# DronePCB_1.net
KiCad netlist of a schematic drawn in Altium Designer
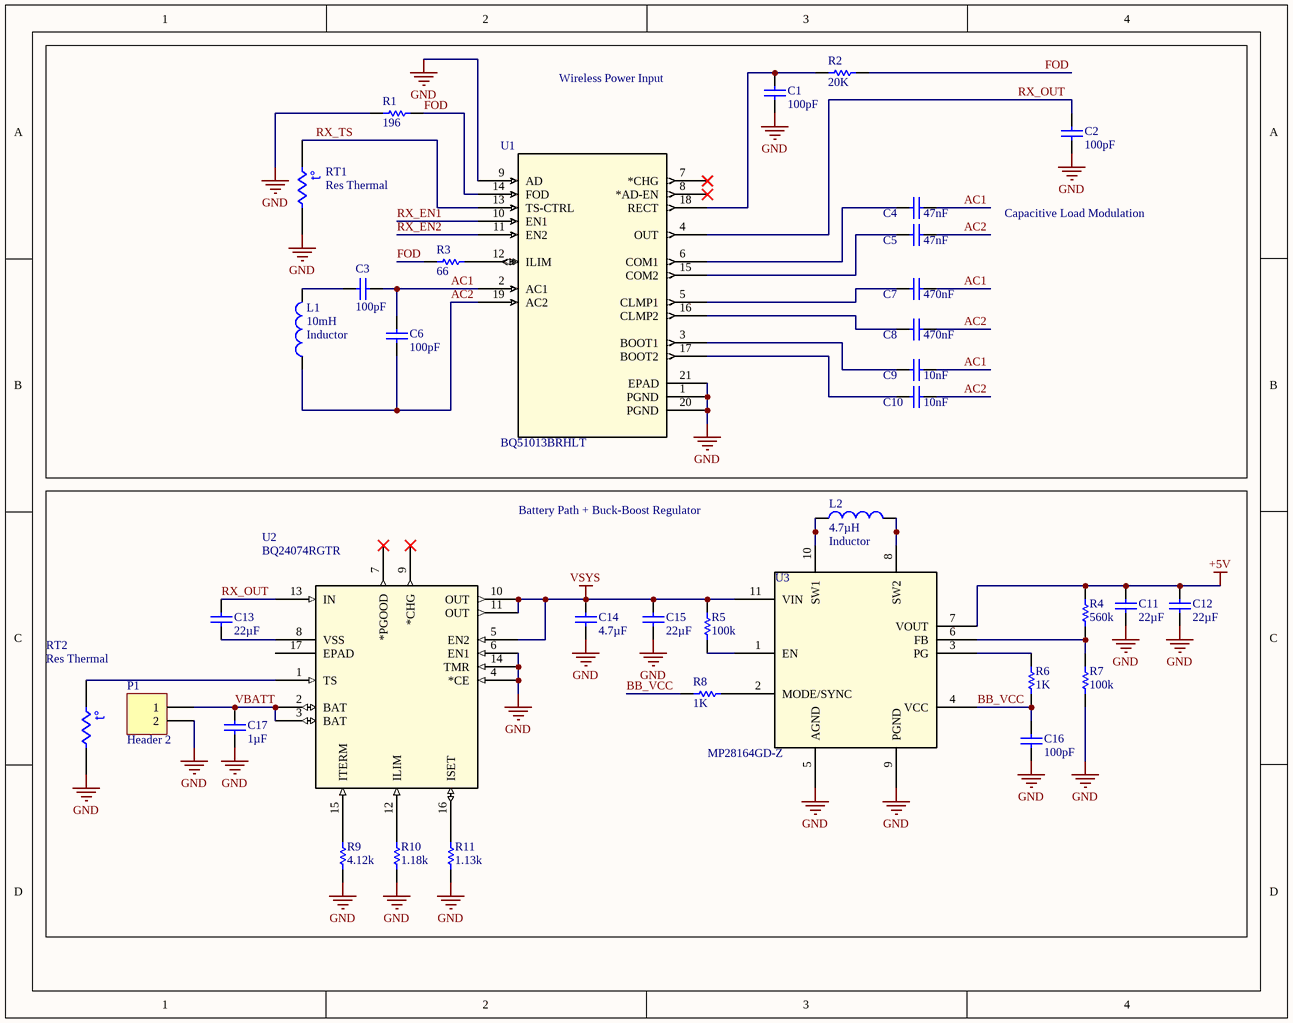
[diagram p0: DronePCB_1.SchDoc]

(export (version "E")
  (design (tool "Eeschema 10.0.6"))
  (components
    (comp (ref "C1")
      (value "100pF")
      (footprint "RAD-0.3")
      (description "Capacitor")
      (fields (field (name "Comment") "Cap") (field (name "PUBLISHER") "Altium Limited"))
      (libsource (lib "Miscellaneous Devices") (part "Cap"))
    )
    (comp (ref "C2")
      (value "100pF")
      (footprint "RAD-0.3")
      (description "Capacitor")
      (fields (field (name "Comment") "Cap") (field (name "PUBLISHER") "Altium Limited"))
      (libsource (lib "Miscellaneous Devices") (part "Cap"))
    )
    (comp (ref "C3")
      (value "100pF")
      (footprint "RAD-0.3")
      (description "Capacitor")
      (fields (field (name "Comment") "Cap") (field (name "PUBLISHER") "Altium Limited"))
      (libsource (lib "Miscellaneous Devices") (part "Cap"))
    )
    (comp (ref "C4")
      (value "47nF")
      (footprint "RAD-0.3")
      (description "Capacitor")
      (fields (field (name "Comment") "Cap") (field (name "PUBLISHER") "Altium Limited"))
      (libsource (lib "Miscellaneous Devices") (part "Cap"))
    )
    (comp (ref "C5")
      (value "47nF")
      (footprint "RAD-0.3")
      (description "Capacitor")
      (fields (field (name "Comment") "Cap") (field (name "PUBLISHER") "Altium Limited"))
      (libsource (lib "Miscellaneous Devices") (part "Cap"))
    )
    (comp (ref "C6")
      (value "100pF")
      (footprint "RAD-0.3")
      (description "Capacitor")
      (fields (field (name "Comment") "Cap") (field (name "PUBLISHER") "Altium Limited"))
      (libsource (lib "Miscellaneous Devices") (part "Cap"))
    )
    (comp (ref "C7")
      (value "470nF")
      (footprint "RAD-0.3")
      (description "Capacitor")
      (fields (field (name "Comment") "Cap") (field (name "PUBLISHER") "Altium Limited"))
      (libsource (lib "Miscellaneous Devices") (part "Cap"))
    )
    (comp (ref "C8")
      (value "470nF")
      (footprint "RAD-0.3")
      (description "Capacitor")
      (fields (field (name "Comment") "Cap") (field (name "PUBLISHER") "Altium Limited"))
      (libsource (lib "Miscellaneous Devices") (part "Cap"))
    )
    (comp (ref "C9")
      (value "10nF")
      (footprint "RAD-0.3")
      (description "Capacitor")
      (fields (field (name "Comment") "Cap") (field (name "PUBLISHER") "Altium Limited"))
      (libsource (lib "Miscellaneous Devices") (part "Cap"))
    )
    (comp (ref "C10")
      (value "10nF")
      (footprint "RAD-0.3")
      (description "Capacitor")
      (fields (field (name "Comment") "Cap") (field (name "PUBLISHER") "Altium Limited"))
      (libsource (lib "Miscellaneous Devices") (part "Cap"))
    )
    (comp (ref "C11")
      (value "22µF")
      (footprint "RAD-0.3")
      (description "Capacitor")
      (fields (field (name "Comment") "Cap") (field (name "PUBLISHER") "Altium Limited"))
      (libsource (lib "Miscellaneous Devices") (part "Cap"))
    )
    (comp (ref "C12")
      (value "22µF")
      (footprint "RAD-0.3")
      (description "Capacitor")
      (fields (field (name "Comment") "Cap") (field (name "PUBLISHER") "Altium Limited"))
      (libsource (lib "Miscellaneous Devices") (part "Cap"))
    )
    (comp (ref "C13")
      (value "22µF")
      (footprint "RAD-0.3")
      (description "Capacitor")
      (fields (field (name "Comment") "Cap") (field (name "PUBLISHER") "Altium Limited"))
      (libsource (lib "Miscellaneous Devices") (part "Cap"))
    )
    (comp (ref "C14")
      (value "4.7µF")
      (footprint "RAD-0.3")
      (description "Capacitor")
      (fields (field (name "Comment") "Cap") (field (name "PUBLISHER") "Altium Limited"))
      (libsource (lib "Miscellaneous Devices") (part "Cap"))
    )
    (comp (ref "C15")
      (value "22µF")
      (footprint "RAD-0.3")
      (description "Capacitor")
      (fields (field (name "Comment") "Cap") (field (name "PUBLISHER") "Altium Limited"))
      (libsource (lib "Miscellaneous Devices") (part "Cap"))
    )
    (comp (ref "C16")
      (value "100pF")
      (footprint "RAD-0.3")
      (description "Capacitor")
      (fields (field (name "Comment") "Cap") (field (name "PUBLISHER") "Altium Limited"))
      (libsource (lib "Miscellaneous Devices") (part "Cap"))
    )
    (comp (ref "C17")
      (value "1µF")
      (footprint "RAD-0.3")
      (description "Capacitor")
      (fields (field (name "Comment") "Cap") (field (name "PUBLISHER") "Altium Limited"))
      (libsource (lib "Miscellaneous Devices") (part "Cap"))
    )
    (comp (ref "L1")
      (value "Inductor")
      (footprint "0402-A")
      (fields (field (name "ALTIUM_VALUE") "10mH") (field (name "PUBLISHER") "Altium Limited"))
      (libsource (lib "Miscellaneous Devices") (part "Inductor"))
    )
    (comp (ref "L2")
      (value "Inductor")
      (footprint "0402-A")
      (fields (field (name "ALTIUM_VALUE") "4.7µH") (field (name "PUBLISHER") "Altium Limited"))
      (libsource (lib "Miscellaneous Devices") (part "Inductor"))
    )
    (comp (ref "P1")
      (value "Header 2")
      (footprint "CUI_TB002-500-02BE")
      (description "Header, 2-Pin")
      (fields (field (name "PUBLISHER") "Altium Limited"))
      (libsource (lib "Miscellaneous Connectors") (part "Header 2"))
    )
    (comp (ref "R1")
      (value "196")
      (footprint "AXIAL-0.3")
      (description "Resistor")
      (fields (field (name "Comment") "Res1") (field (name "PUBLISHER") "Altium Limited"))
      (libsource (lib "Miscellaneous Devices") (part "Res1"))
    )
    (comp (ref "R2")
      (value "20K")
      (footprint "AXIAL-0.3")
      (description "Resistor")
      (fields (field (name "Comment") "Res1") (field (name "PUBLISHER") "Altium Limited"))
      (libsource (lib "Miscellaneous Devices") (part "Res1"))
    )
    (comp (ref "R3")
      (value "66")
      (footprint "AXIAL-0.3")
      (description "Resistor")
      (fields (field (name "Comment") "Res1") (field (name "PUBLISHER") "Altium Limited"))
      (libsource (lib "Miscellaneous Devices") (part "Res1"))
    )
    (comp (ref "R4")
      (value "560k")
      (footprint "AXIAL-0.3")
      (description "Resistor")
      (fields (field (name "Comment") "Res1") (field (name "PUBLISHER") "Altium Limited"))
      (libsource (lib "Miscellaneous Devices") (part "Res1"))
    )
    (comp (ref "R5")
      (value "100k")
      (footprint "AXIAL-0.3")
      (description "Resistor")
      (fields (field (name "Comment") "Res1") (field (name "PUBLISHER") "Altium Limited"))
      (libsource (lib "Miscellaneous Devices") (part "Res1"))
    )
    (comp (ref "R6")
      (value "1K")
      (footprint "AXIAL-0.3")
      (description "Resistor")
      (fields (field (name "Comment") "Res1") (field (name "PUBLISHER") "Altium Limited"))
      (libsource (lib "Miscellaneous Devices") (part "Res1"))
    )
    (comp (ref "R7")
      (value "100k")
      (footprint "AXIAL-0.3")
      (description "Resistor")
      (fields (field (name "Comment") "Res1") (field (name "PUBLISHER") "Altium Limited"))
      (libsource (lib "Miscellaneous Devices") (part "Res1"))
    )
    (comp (ref "R8")
      (value "1K")
      (footprint "AXIAL-0.3")
      (description "Resistor")
      (fields (field (name "Comment") "Res1") (field (name "PUBLISHER") "Altium Limited"))
      (libsource (lib "Miscellaneous Devices") (part "Res1"))
    )
    (comp (ref "R9")
      (value "4.12k")
      (footprint "AXIAL-0.3")
      (description "Resistor")
      (fields (field (name "Comment") "Res1") (field (name "PUBLISHER") "Altium Limited"))
      (libsource (lib "Miscellaneous Devices") (part "Res1"))
    )
    (comp (ref "R10")
      (value "1.18k")
      (footprint "AXIAL-0.3")
      (description "Resistor")
      (fields (field (name "Comment") "Res1") (field (name "PUBLISHER") "Altium Limited"))
      (libsource (lib "Miscellaneous Devices") (part "Res1"))
    )
    (comp (ref "R11")
      (value "1.13k")
      (footprint "AXIAL-0.3")
      (description "Resistor")
      (fields (field (name "Comment") "Res1") (field (name "PUBLISHER") "Altium Limited"))
      (libsource (lib "Miscellaneous Devices") (part "Res1"))
    )
    (comp (ref "RT1")
      (value "Res Thermal")
      (footprint "6-0805_N")
      (description "Thermistor")
      (fields (field (name "PUBLISHER") "Altium Limited"))
      (libsource (lib "Miscellaneous Devices") (part "Res Thermal"))
    )
    (comp (ref "RT2")
      (value "Res Thermal")
      (footprint "6-0805_N")
      (description "Thermistor")
      (fields (field (name "PUBLISHER") "Altium Limited"))
      (libsource (lib "Miscellaneous Devices") (part "Res Thermal"))
    )
    (comp (ref "U1")
      (value "BQ51013BRHLT")
      (footprint "RHL20_2P05X3P05")
      (description "WPC 1.1 Compatible Fully integrated Wireless power Receiver IC 20-VQFN 0 to 125")
      (fields (field (name "COPYRIGHT") "Copyright (C) 2026 Ultra Librarian. All rights reserved."))
      (libsource (lib "DronePCB_Main") (part "BQ51013BRHLT"))
    )
    (comp (ref "U2")
      (value "BQ24074RGTR")
      (footprint "RGT16_1P7X1P7")
      (fields (field (name "COPYRIGHT") "Copyright (C) 2026 Ultra Librarian. All rights reserved."))
      (libsource (lib "DronePCB_Main") (part "BQ24074RGTR"))
    )
    (comp (ref "U3")
      (value "MP28164GD-Z")
      (footprint "QFN-11_MP28164_MNP")
      (description "High-Efficiency Single-Inductor Buck-Boost Converter with 4.2A Switches")
      (fields (field (name "COPYRIGHT") "Copyright (C) 2025 Ultra Librarian. All rights reserved."))
      (libsource (lib "DronePCB_Main") (part "MP28164GD-Z"))
    )
  )
  (nets
    (net (code "1") (name "+5V") (class "Default")
      (node (ref "C11") (pin "2") (pinfunction "2_2") (pintype "passive"))
      (node (ref "C12") (pin "2") (pinfunction "2_2") (pintype "passive"))
      (node (ref "R4") (pin "2") (pinfunction "2_2") (pintype "passive"))
      (node (ref "U3") (pin "7") (pinfunction "VOUT_7") (pintype "power_in"))
    )
    (net (code "2") (name "/AC1") (class "Default")
      (node (ref "C3") (pin "2") (pinfunction "2_2") (pintype "passive"))
      (node (ref "C4") (pin "2") (pinfunction "2_2") (pintype "passive"))
      (node (ref "C6") (pin "2") (pinfunction "2_2") (pintype "passive"))
      (node (ref "C7") (pin "2") (pinfunction "2_2") (pintype "passive"))
      (node (ref "C9") (pin "2") (pinfunction "2_2") (pintype "passive"))
      (node (ref "U1") (pin "2") (pinfunction "AC1_2") (pintype "input"))
    )
    (net (code "3") (name "/AC2") (class "Default")
      (node (ref "C10") (pin "2") (pinfunction "2_2") (pintype "passive"))
      (node (ref "C5") (pin "2") (pinfunction "2_2") (pintype "passive"))
      (node (ref "C6") (pin "1") (pinfunction "1_1") (pintype "passive"))
      (node (ref "C8") (pin "2") (pinfunction "2_2") (pintype "passive"))
      (node (ref "L1") (pin "1") (pinfunction "1_1") (pintype "passive"))
      (node (ref "U1") (pin "19") (pinfunction "AC2_19") (pintype "input"))
    )
    (net (code "4") (name "/BB_VCC") (class "Default")
      (node (ref "C16") (pin "2") (pinfunction "2_2") (pintype "passive"))
      (node (ref "R6") (pin "1") (pinfunction "1_1") (pintype "passive"))
      (node (ref "R8") (pin "2") (pinfunction "2_2") (pintype "passive"))
      (node (ref "U3") (pin "4") (pinfunction "VCC_4") (pintype "power_in"))
    )
    (net (code "5") (name "/FOD") (class "Default")
      (node (ref "R1") (pin "2") (pinfunction "2_2") (pintype "passive"))
      (node (ref "R2") (pin "2") (pinfunction "2_2") (pintype "passive"))
      (node (ref "R3") (pin "1") (pinfunction "1_1") (pintype "passive"))
      (node (ref "U1") (pin "14") (pinfunction "FOD_14") (pintype "input"))
    )
    (net (code "6") (name "/RX_EN1") (class "Default")
      (node (ref "U1") (pin "10") (pinfunction "EN1_10") (pintype "input"))
    )
    (net (code "7") (name "/RX_EN2") (class "Default")
      (node (ref "U1") (pin "11") (pinfunction "EN2_11") (pintype "input"))
    )
    (net (code "8") (name "/RX_OUT") (class "Default")
      (node (ref "C13") (pin "2") (pinfunction "2_2") (pintype "passive"))
      (node (ref "C2") (pin "1") (pinfunction "1_1") (pintype "passive"))
      (node (ref "U1") (pin "4") (pinfunction "OUT_4") (pintype "output"))
      (node (ref "U2") (pin "13") (pinfunction "IN_13") (pintype "input"))
    )
    (net (code "9") (name "/RX_TS") (class "Default")
      (node (ref "RT1") (pin "1") (pinfunction "1_1") (pintype "passive"))
      (node (ref "U1") (pin "13") (pinfunction "TS-CTRL_13") (pintype "input"))
    )
    (net (code "10") (name "/VBATT") (class "Default")
      (node (ref "C17") (pin "2") (pinfunction "2_2") (pintype "passive"))
      (node (ref "P1") (pin "1") (pinfunction "1_1") (pintype "passive"))
      (node (ref "U2") (pin "2") (pinfunction "BAT_2") (pintype "bidirectional"))
      (node (ref "U2") (pin "3") (pinfunction "BAT_3") (pintype "bidirectional"))
    )
    (net (code "11") (name "GND") (class "Default")
      (node (ref "C1") (pin "2") (pinfunction "2_2") (pintype "passive"))
      (node (ref "C11") (pin "1") (pinfunction "1_1") (pintype "passive"))
      (node (ref "C12") (pin "1") (pinfunction "1_1") (pintype "passive"))
      (node (ref "C14") (pin "1") (pinfunction "1_1") (pintype "passive"))
      (node (ref "C15") (pin "1") (pinfunction "1_1") (pintype "passive"))
      (node (ref "C16") (pin "1") (pinfunction "1_1") (pintype "passive"))
      (node (ref "C17") (pin "1") (pinfunction "1_1") (pintype "passive"))
      (node (ref "C2") (pin "2") (pinfunction "2_2") (pintype "passive"))
      (node (ref "P1") (pin "2") (pinfunction "2_2") (pintype "passive"))
      (node (ref "R1") (pin "1") (pinfunction "1_1") (pintype "passive"))
      (node (ref "R10") (pin "1") (pinfunction "1_1") (pintype "passive"))
      (node (ref "R11") (pin "1") (pinfunction "1_1") (pintype "passive"))
      (node (ref "R7") (pin "1") (pinfunction "1_1") (pintype "passive"))
      (node (ref "R9") (pin "1") (pinfunction "1_1") (pintype "passive"))
      (node (ref "RT1") (pin "2") (pinfunction "2_2") (pintype "passive"))
      (node (ref "RT2") (pin "2") (pinfunction "2_2") (pintype "passive"))
      (node (ref "U1") (pin "1") (pinfunction "PGND_1") (pintype "power_in"))
      (node (ref "U1") (pin "20") (pinfunction "PGND_20") (pintype "power_in"))
      (node (ref "U1") (pin "21") (pinfunction "EPAD_21") (pintype "passive"))
      (node (ref "U1") (pin "9") (pinfunction "AD_9") (pintype "input"))
      (node (ref "U2") (pin "14") (pinfunction "TMR_14") (pintype "input"))
      (node (ref "U2") (pin "4") (pinfunction "*CE_4") (pintype "input"))
      (node (ref "U2") (pin "6") (pinfunction "EN1_6") (pintype "input"))
      (node (ref "U3") (pin "5") (pinfunction "AGND_5") (pintype "power_in"))
      (node (ref "U3") (pin "9") (pinfunction "PGND_9") (pintype "power_in"))
    )
    (net (code "12") (name "Net-(C3-Pad1)") (class "Default")
      (node (ref "C3") (pin "1") (pinfunction "1_1") (pintype "passive"))
      (node (ref "L1") (pin "2") (pinfunction "2_2") (pintype "passive"))
    )
    (net (code "13") (name "Net-(U1-BOOT1)") (class "Default")
      (node (ref "C9") (pin "1") (pinfunction "1_1") (pintype "passive"))
      (node (ref "U1") (pin "3") (pinfunction "BOOT1_3") (pintype "output"))
    )
    (net (code "14") (name "Net-(U1-BOOT2)") (class "Default")
      (node (ref "C10") (pin "1") (pinfunction "1_1") (pintype "passive"))
      (node (ref "U1") (pin "17") (pinfunction "BOOT2_17") (pintype "output"))
    )
    (net (code "15") (name "Net-(U1-CLMP1)") (class "Default")
      (node (ref "C7") (pin "1") (pinfunction "1_1") (pintype "passive"))
      (node (ref "U1") (pin "5") (pinfunction "CLMP1_5") (pintype "output"))
    )
    (net (code "16") (name "Net-(U1-CLMP2)") (class "Default")
      (node (ref "C8") (pin "1") (pinfunction "1_1") (pintype "passive"))
      (node (ref "U1") (pin "16") (pinfunction "CLMP2_16") (pintype "output"))
    )
    (net (code "17") (name "Net-(U1-COM1)") (class "Default")
      (node (ref "C4") (pin "1") (pinfunction "1_1") (pintype "passive"))
      (node (ref "U1") (pin "6") (pinfunction "COM1_6") (pintype "output"))
    )
    (net (code "18") (name "Net-(U1-COM2)") (class "Default")
      (node (ref "C5") (pin "1") (pinfunction "1_1") (pintype "passive"))
      (node (ref "U1") (pin "15") (pinfunction "COM2_15") (pintype "output"))
    )
    (net (code "19") (name "Net-(U1-ILIM)") (class "Default")
      (node (ref "R3") (pin "2") (pinfunction "2_2") (pintype "passive"))
      (node (ref "U1") (pin "12") (pinfunction "ILIM_12") (pintype "bidirectional"))
    )
    (net (code "20") (name "Net-(U1-RECT)") (class "Default")
      (node (ref "C1") (pin "1") (pinfunction "1_1") (pintype "passive"))
      (node (ref "R2") (pin "1") (pinfunction "1_1") (pintype "passive"))
      (node (ref "U1") (pin "18") (pinfunction "RECT_18") (pintype "output"))
    )
    (net (code "21") (name "Net-(U2-ILIM)") (class "Default")
      (node (ref "R10") (pin "2") (pinfunction "2_2") (pintype "passive"))
      (node (ref "U2") (pin "12") (pinfunction "ILIM_12") (pintype "input"))
    )
    (net (code "22") (name "Net-(U2-ISET)") (class "Default")
      (node (ref "R11") (pin "2") (pinfunction "2_2") (pintype "passive"))
      (node (ref "U2") (pin "16") (pinfunction "ISET_16") (pintype "bidirectional"))
    )
    (net (code "23") (name "Net-(U2-ITERM)") (class "Default")
      (node (ref "R9") (pin "2") (pinfunction "2_2") (pintype "passive"))
      (node (ref "U2") (pin "15") (pinfunction "ITERM_15") (pintype "input"))
    )
    (net (code "24") (name "Net-(U2-TS)") (class "Default")
      (node (ref "RT2") (pin "1") (pinfunction "1_1") (pintype "passive"))
      (node (ref "U2") (pin "1") (pinfunction "TS_1") (pintype "input"))
    )
    (net (code "25") (name "Net-(U2-VSS)") (class "Default")
      (node (ref "C13") (pin "1") (pinfunction "1_1") (pintype "passive"))
      (node (ref "U2") (pin "8") (pinfunction "VSS_8") (pintype "power_in"))
    )
    (net (code "26") (name "Net-(U3-EN)") (class "Default")
      (node (ref "R5") (pin "2") (pinfunction "2_2") (pintype "passive"))
      (node (ref "U3") (pin "1") (pinfunction "EN_1") (pintype "passive"))
    )
    (net (code "27") (name "Net-(U3-FB)") (class "Default")
      (node (ref "R4") (pin "1") (pinfunction "1_1") (pintype "passive"))
      (node (ref "R7") (pin "2") (pinfunction "2_2") (pintype "passive"))
      (node (ref "U3") (pin "6") (pinfunction "FB_6") (pintype "passive"))
    )
    (net (code "28") (name "Net-(U3-MODE{slash}SYNC)") (class "Default")
      (node (ref "R8") (pin "1") (pinfunction "1_1") (pintype "passive"))
      (node (ref "U3") (pin "2") (pinfunction "MODE/SYNC_2") (pintype "passive"))
    )
    (net (code "29") (name "Net-(U3-PG)") (class "Default")
      (node (ref "R6") (pin "2") (pinfunction "2_2") (pintype "passive"))
      (node (ref "U3") (pin "3") (pinfunction "PG_3") (pintype "passive"))
    )
    (net (code "30") (name "Net-(U3-SW1)") (class "Default")
      (node (ref "L2") (pin "1") (pinfunction "1_1") (pintype "passive"))
      (node (ref "U3") (pin "10") (pinfunction "SW1_10") (pintype "passive"))
    )
    (net (code "31") (name "Net-(U3-SW2)") (class "Default")
      (node (ref "L2") (pin "2") (pinfunction "2_2") (pintype "passive"))
      (node (ref "U3") (pin "8") (pinfunction "SW2_8") (pintype "passive"))
    )
    (net (code "32") (name "VSYS") (class "Default")
      (node (ref "C14") (pin "2") (pinfunction "2_2") (pintype "passive"))
      (node (ref "C15") (pin "2") (pinfunction "2_2") (pintype "passive"))
      (node (ref "R5") (pin "1") (pinfunction "1_1") (pintype "passive"))
      (node (ref "U2") (pin "10") (pinfunction "OUT_10") (pintype "output"))
      (node (ref "U2") (pin "11") (pinfunction "OUT_11") (pintype "output"))
      (node (ref "U2") (pin "5") (pinfunction "EN2_5") (pintype "input"))
      (node (ref "U3") (pin "11") (pinfunction "VIN_11") (pintype "power_in"))
    )
    (net (code "33") (name "unconnected-(U1-*AD-EN-Pad8)") (class "Default")
      (node (ref "U1") (pin "8") (pinfunction "*AD-EN_8") (pintype "output+no_connect"))
    )
    (net (code "34") (name "unconnected-(U1-*CHG-Pad7)") (class "Default")
      (node (ref "U1") (pin "7") (pinfunction "*CHG_7") (pintype "output+no_connect"))
    )
    (net (code "35") (name "unconnected-(U2-*CHG-Pad9)") (class "Default")
      (node (ref "U2") (pin "9") (pinfunction "*CHG_9") (pintype "output+no_connect"))
    )
    (net (code "36") (name "unconnected-(U2-*PGOOD-Pad7)") (class "Default")
      (node (ref "U2") (pin "7") (pinfunction "*PGOOD_7") (pintype "output+no_connect"))
    )
    (net (code "37") (name "unconnected-(U2-EPAD-Pad17)") (class "Default")
      (node (ref "U2") (pin "17") (pinfunction "EPAD_17") (pintype "power_in"))
    )
  )
)
